# coolRoof_concentrateur_exterieur.net
KiCad netlist of a schematic drawn in EAGLE
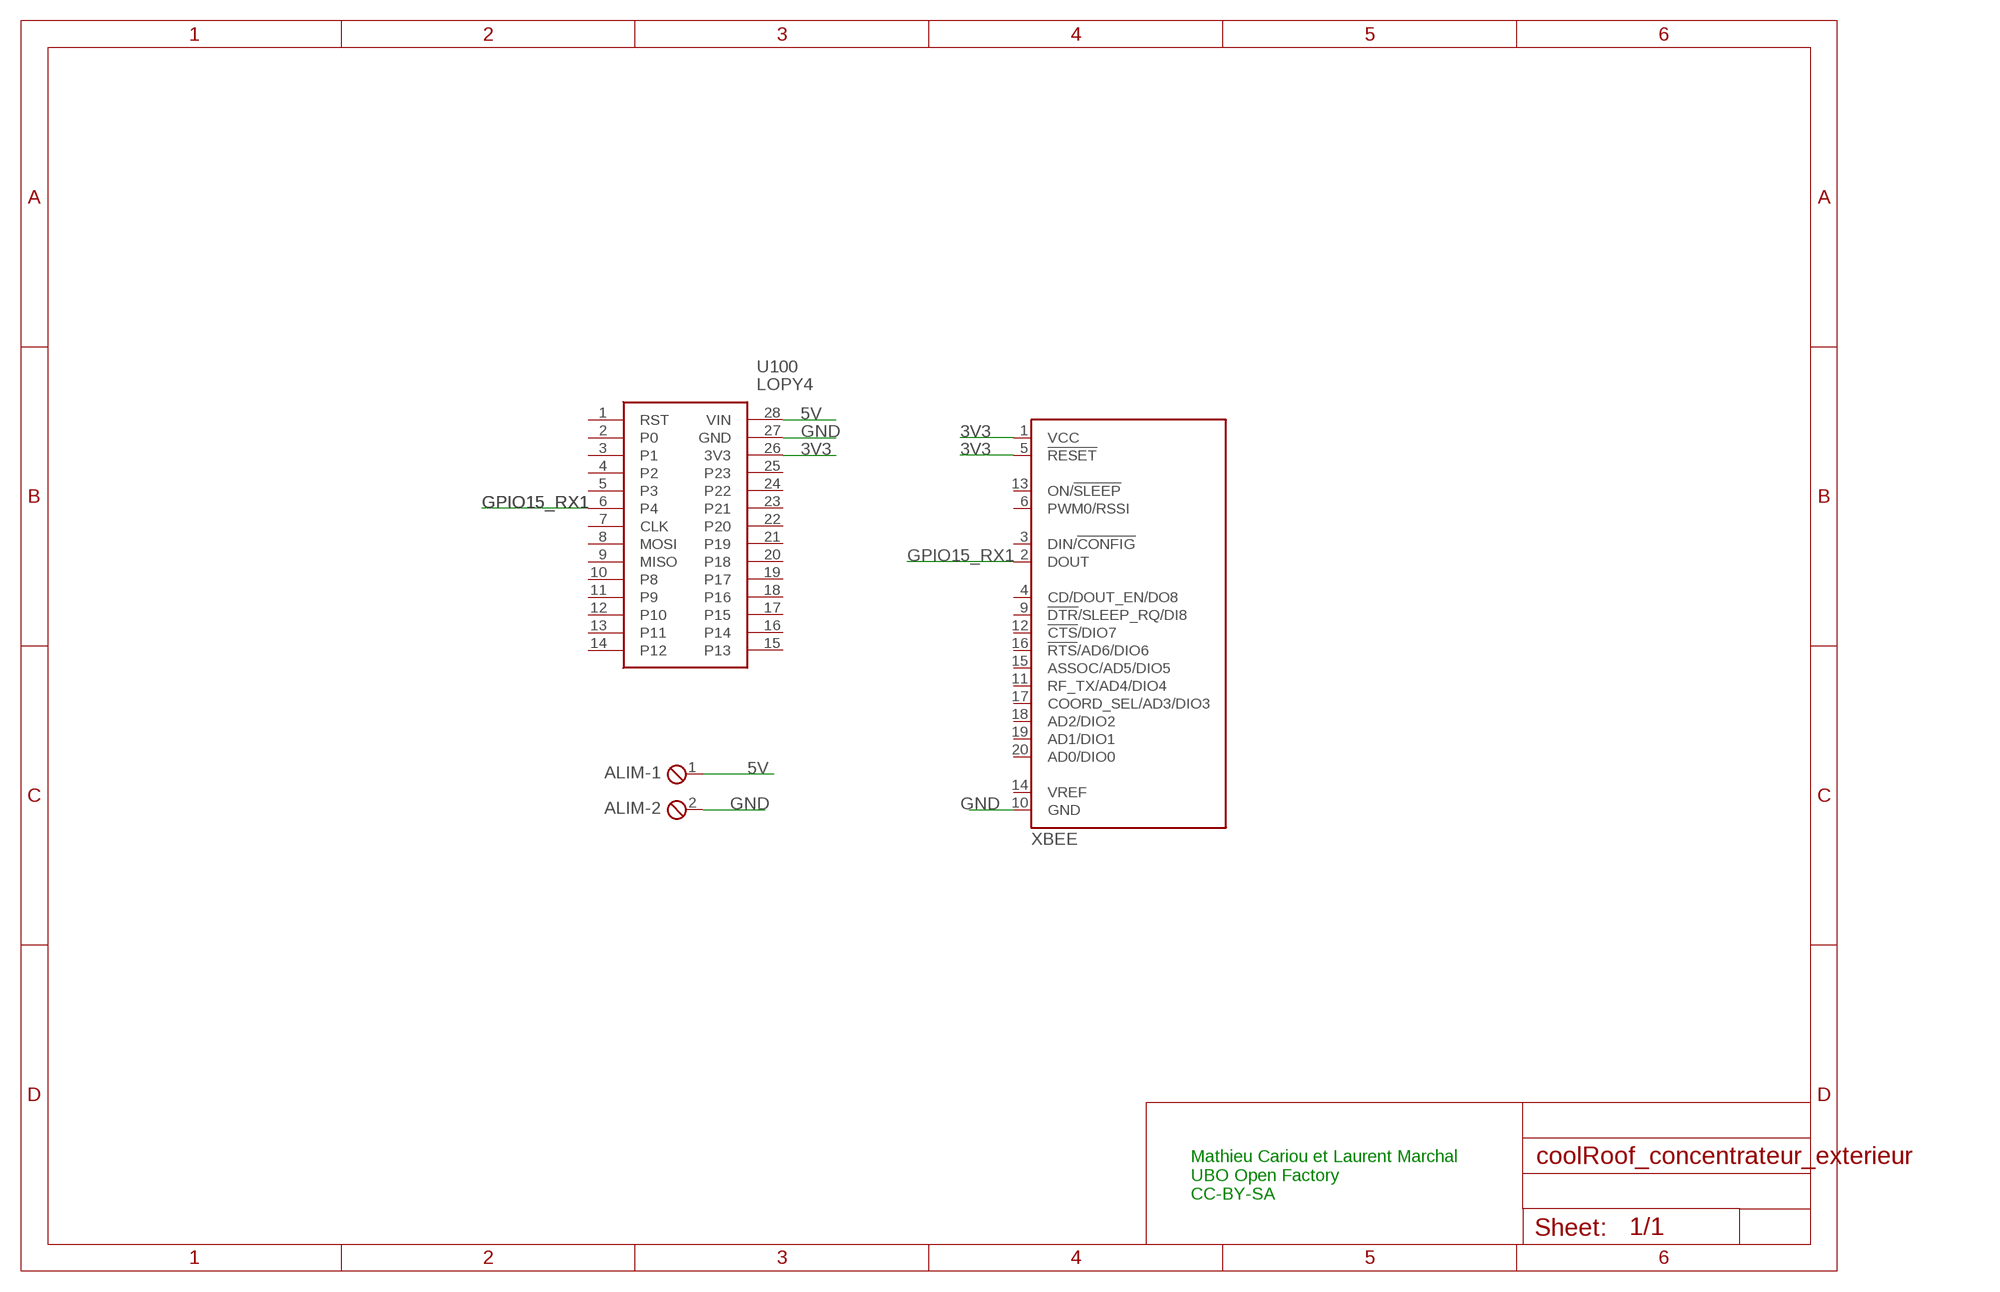
[diagram p0: schematic, sheet 1]

(export (version "E")
  (design (tool "Eeschema 10.0.6"))
  (components
    (comp (ref "ALIM")
      (value "MPT2")
      (footprint "eagle-import:2POL254")
      (libsource (lib "eagle-import") (part "MPT2"))
    )
    (comp (ref "U100")
      (value "LOPY4")
      (footprint "eagle-import:LOPY4")
      (fields (field (name "MOUSER_PART_NUMBER") "365-LOPY4"))
      (libsource (lib "eagle-import") (part "LOPY4"))
    )
    (comp (ref "U101")
      (value "XBEE")
      (footprint "eagle-import:XBEE")
      (fields (field (name "MPN") "XBP24-Z7UIT-004"))
      (libsource (lib "eagle-import") (part "XBEE"))
    )
  )
  (nets
    (net (code "1") (name "/3V3") (class "Default")
      (node (ref "U100") (pin "26") (pinfunction "3V3_26") (pintype "bidirectional"))
      (node (ref "U101") (pin "1") (pinfunction "VCC_1") (pintype "power_in"))
      (node (ref "U101") (pin "5") (pinfunction "~{RESET}_5") (pintype "input"))
    )
    (net (code "2") (name "/5V") (class "Default")
      (node (ref "ALIM") (pin "1") (pinfunction "1_1") (pintype "passive"))
      (node (ref "U100") (pin "28") (pinfunction "VIN_28") (pintype "bidirectional"))
    )
    (net (code "3") (name "/GND") (class "Default")
      (node (ref "ALIM") (pin "2") (pinfunction "1_2") (pintype "passive"))
      (node (ref "U100") (pin "27") (pinfunction "GND_27") (pintype "bidirectional"))
      (node (ref "U101") (pin "10") (pinfunction "GND_10") (pintype "power_in"))
    )
    (net (code "4") (name "/GPIO15_RX1") (class "Default")
      (node (ref "U100") (pin "6") (pinfunction "P4_6") (pintype "bidirectional"))
      (node (ref "U101") (pin "2") (pinfunction "DOUT_2") (pintype "output"))
    )
    (net (code "5") (name "unconnected-(U100-CLK-Pad7)") (class "Default")
      (node (ref "U100") (pin "7") (pinfunction "CLK_7") (pintype "bidirectional"))
    )
    (net (code "6") (name "unconnected-(U100-MISO-Pad9)") (class "Default")
      (node (ref "U100") (pin "9") (pinfunction "MISO_9") (pintype "bidirectional"))
    )
    (net (code "7") (name "unconnected-(U100-MOSI-Pad8)") (class "Default")
      (node (ref "U100") (pin "8") (pinfunction "MOSI_8") (pintype "bidirectional"))
    )
    (net (code "8") (name "unconnected-(U100-P0-Pad2)") (class "Default")
      (node (ref "U100") (pin "2") (pinfunction "P0_2") (pintype "bidirectional"))
    )
    (net (code "9") (name "unconnected-(U100-P1-Pad3)") (class "Default")
      (node (ref "U100") (pin "3") (pinfunction "P1_3") (pintype "bidirectional"))
    )
    (net (code "10") (name "unconnected-(U100-P2-Pad4)") (class "Default")
      (node (ref "U100") (pin "4") (pinfunction "P2_4") (pintype "bidirectional"))
    )
    (net (code "11") (name "unconnected-(U100-P3-Pad5)") (class "Default")
      (node (ref "U100") (pin "5") (pinfunction "P3_5") (pintype "bidirectional"))
    )
    (net (code "12") (name "unconnected-(U100-P8-Pad10)") (class "Default")
      (node (ref "U100") (pin "10") (pinfunction "P8_10") (pintype "bidirectional"))
    )
    (net (code "13") (name "unconnected-(U100-P9-Pad11)") (class "Default")
      (node (ref "U100") (pin "11") (pinfunction "P9_11") (pintype "bidirectional"))
    )
    (net (code "14") (name "unconnected-(U100-P10-Pad12)") (class "Default")
      (node (ref "U100") (pin "12") (pinfunction "P10_12") (pintype "bidirectional"))
    )
    (net (code "15") (name "unconnected-(U100-P11-Pad13)") (class "Default")
      (node (ref "U100") (pin "13") (pinfunction "P11_13") (pintype "bidirectional"))
    )
    (net (code "16") (name "unconnected-(U100-P12-Pad14)") (class "Default")
      (node (ref "U100") (pin "14") (pinfunction "P12_14") (pintype "bidirectional"))
    )
    (net (code "17") (name "unconnected-(U100-P13-Pad15)") (class "Default")
      (node (ref "U100") (pin "15") (pinfunction "P13_15") (pintype "bidirectional"))
    )
    (net (code "18") (name "unconnected-(U100-P14-Pad16)") (class "Default")
      (node (ref "U100") (pin "16") (pinfunction "P14_16") (pintype "bidirectional"))
    )
    (net (code "19") (name "unconnected-(U100-P15-Pad17)") (class "Default")
      (node (ref "U100") (pin "17") (pinfunction "P15_17") (pintype "bidirectional"))
    )
    (net (code "20") (name "unconnected-(U100-P16-Pad18)") (class "Default")
      (node (ref "U100") (pin "18") (pinfunction "P16_18") (pintype "bidirectional"))
    )
    (net (code "21") (name "unconnected-(U100-P17-Pad19)") (class "Default")
      (node (ref "U100") (pin "19") (pinfunction "P17_19") (pintype "bidirectional"))
    )
    (net (code "22") (name "unconnected-(U100-P18-Pad20)") (class "Default")
      (node (ref "U100") (pin "20") (pinfunction "P18_20") (pintype "bidirectional"))
    )
    (net (code "23") (name "unconnected-(U100-P19-Pad21)") (class "Default")
      (node (ref "U100") (pin "21") (pinfunction "P19_21") (pintype "bidirectional"))
    )
    (net (code "24") (name "unconnected-(U100-P20-Pad22)") (class "Default")
      (node (ref "U100") (pin "22") (pinfunction "P20_22") (pintype "bidirectional"))
    )
    (net (code "25") (name "unconnected-(U100-P21-Pad23)") (class "Default")
      (node (ref "U100") (pin "23") (pinfunction "P21_23") (pintype "bidirectional"))
    )
    (net (code "26") (name "unconnected-(U100-P22-Pad24)") (class "Default")
      (node (ref "U100") (pin "24") (pinfunction "P22_24") (pintype "bidirectional"))
    )
    (net (code "27") (name "unconnected-(U100-P23-Pad25)") (class "Default")
      (node (ref "U100") (pin "25") (pinfunction "P23_25") (pintype "bidirectional"))
    )
    (net (code "28") (name "unconnected-(U100-RST-Pad1)") (class "Default")
      (node (ref "U100") (pin "1") (pinfunction "RST_1") (pintype "bidirectional"))
    )
    (net (code "29") (name "unconnected-(U101-AD0{slash}DIO0-Pad20)") (class "Default")
      (node (ref "U101") (pin "20") (pinfunction "AD0/DIO0_20") (pintype "bidirectional"))
    )
    (net (code "30") (name "unconnected-(U101-AD1{slash}DIO1-Pad19)") (class "Default")
      (node (ref "U101") (pin "19") (pinfunction "AD1/DIO1_19") (pintype "bidirectional"))
    )
    (net (code "31") (name "unconnected-(U101-AD2{slash}DIO2-Pad18)") (class "Default")
      (node (ref "U101") (pin "18") (pinfunction "AD2/DIO2_18") (pintype "bidirectional"))
    )
    (net (code "32") (name "unconnected-(U101-ASSOC{slash}AD5{slash}DIO5-Pad15)") (class "Default")
      (node (ref "U101") (pin "15") (pinfunction "ASSOC/AD5/DIO5_15") (pintype "bidirectional"))
    )
    (net (code "33") (name "unconnected-(U101-CD{slash}DOUT_EN{slash}DO8-Pad4)") (class "Default")
      (node (ref "U101") (pin "4") (pinfunction "CD/DOUT_EN/DO8_4") (pintype "output"))
    )
    (net (code "34") (name "unconnected-(U101-COORD_SEL{slash}AD3{slash}DIO3-Pad17)") (class "Default")
      (node (ref "U101") (pin "17") (pinfunction "COORD_SEL/AD3/DIO3_17") (pintype "bidirectional"))
    )
    (net (code "35") (name "unconnected-(U101-DIN{slash}~{CONFIG}-Pad3)") (class "Default")
      (node (ref "U101") (pin "3") (pinfunction "DIN/~{CONFIG}_3") (pintype "input"))
    )
    (net (code "36") (name "unconnected-(U101-ON{slash}~{SLEEP}-Pad13)") (class "Default")
      (node (ref "U101") (pin "13") (pinfunction "ON/~{SLEEP}_13") (pintype "output"))
    )
    (net (code "37") (name "unconnected-(U101-PWM0{slash}RSSI-Pad6)") (class "Default")
      (node (ref "U101") (pin "6") (pinfunction "PWM0/RSSI_6") (pintype "output"))
    )
    (net (code "38") (name "unconnected-(U101-RF_TX{slash}AD4{slash}DIO4-Pad11)") (class "Default")
      (node (ref "U101") (pin "11") (pinfunction "RF_TX/AD4/DIO4_11") (pintype "bidirectional"))
    )
    (net (code "39") (name "unconnected-(U101-VREF-Pad14)") (class "Default")
      (node (ref "U101") (pin "14") (pinfunction "VREF_14") (pintype "input"))
    )
    (net (code "40") (name "unconnected-(U101-~{CTS}{slash}DIO7-Pad12)") (class "Default")
      (node (ref "U101") (pin "12") (pinfunction "~{CTS}/DIO7_12") (pintype "bidirectional"))
    )
    (net (code "41") (name "unconnected-(U101-~{DTR}{slash}SLEEP_RQ{slash}DI8-Pad9)") (class "Default")
      (node (ref "U101") (pin "9") (pinfunction "~{DTR}/SLEEP_RQ/DI8_9") (pintype "bidirectional"))
    )
    (net (code "42") (name "unconnected-(U101-~{RTS}{slash}AD6{slash}DIO6-Pad16)") (class "Default")
      (node (ref "U101") (pin "16") (pinfunction "~{RTS}/AD6/DIO6_16") (pintype "bidirectional"))
    )
  )
)
